# blackfin_c_ethernet.net
KiCad netlist of a schematic drawn in Altium Designer
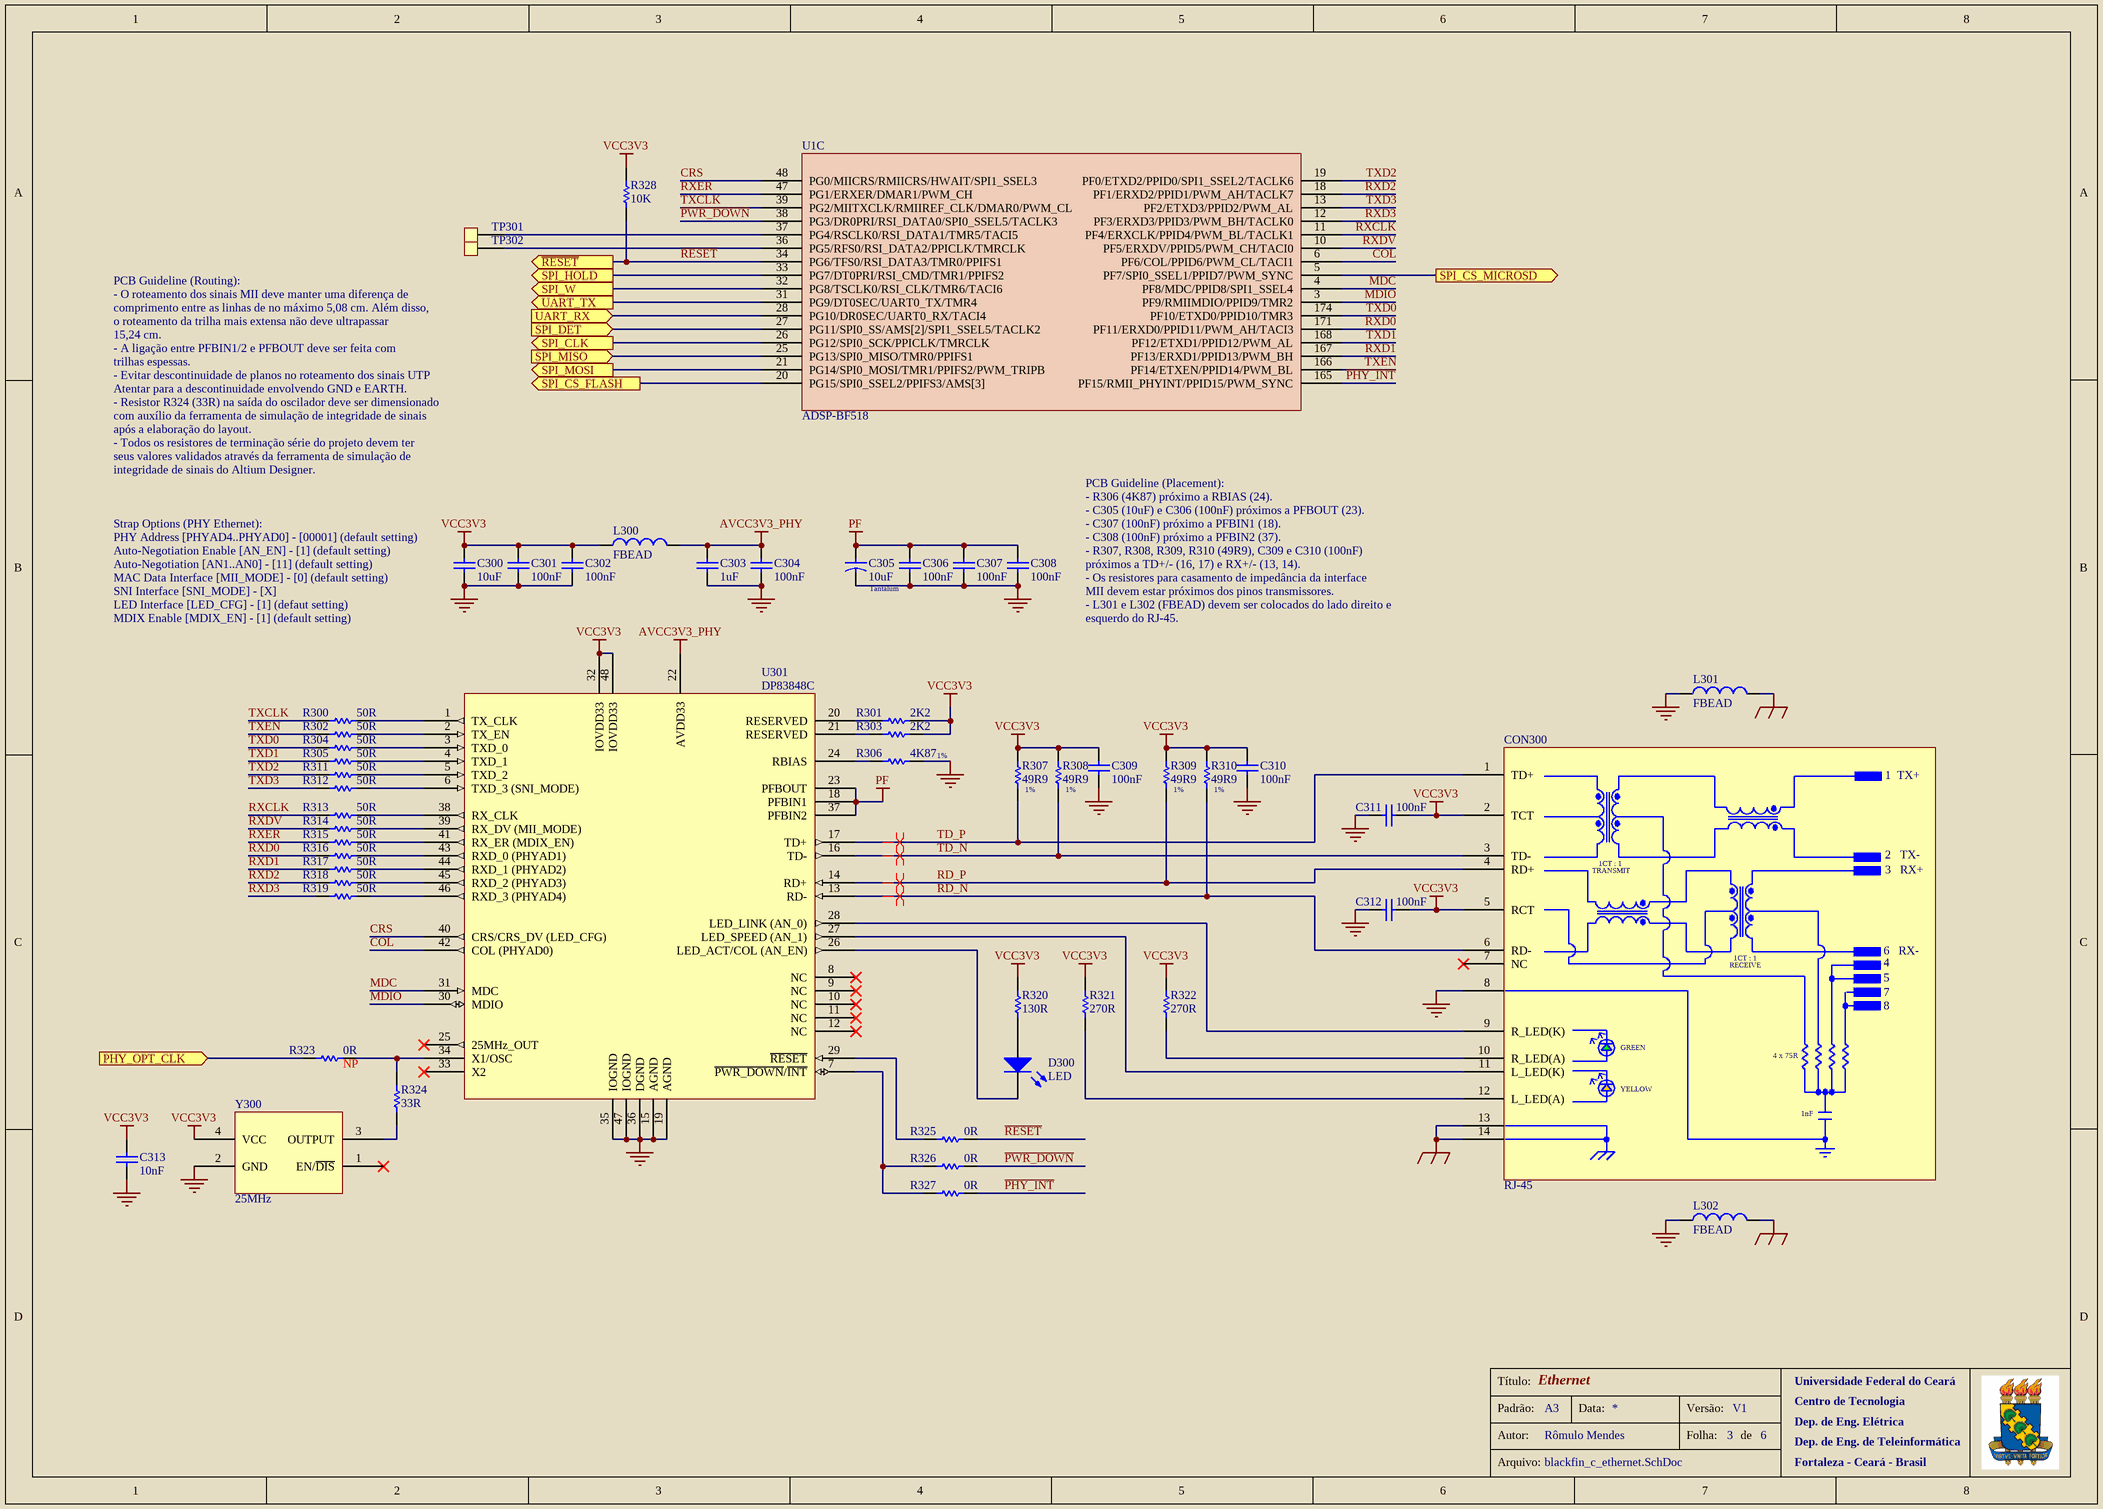
[diagram p0: blackfin_c_ethernet.SchDoc]

(export (version "E")
  (design (tool "Eeschema 10.0.6"))
  (components
    (comp (ref "C300")
      (value "10uF")
      (footprint "blackfin_pcblib:C_0805")
      (fields
        (field (name "EVENDORPART#") "810-C2012Y5V1C106Z")
        (field (name "MANUFACTURER") "TDK")
        (field (name "PART#") "C2012Y5V1C106Z")
      )
      (libsource (lib "blackfin_schlib") (part "Capacitor"))
    )
    (comp (ref "C301")
      (value "100nF")
      (footprint "blackfin_pcblib:C_0603")
      (fields
        (field (name "EVENDORPART#") "81-GRM188R71E104KA01")
        (field (name "MANUFACTURER") "Murata")
        (field (name "PART#") "GRM188R71E104KA01J")
      )
      (libsource (lib "blackfin_schlib") (part "Capacitor"))
    )
    (comp (ref "C302")
      (value "100nF")
      (footprint "blackfin_pcblib:C_0603")
      (fields
        (field (name "EVENDORPART#") "81-GRM188R71E104KA01")
        (field (name "MANUFACTURER") "Murata")
        (field (name "PART#") "GRM188R71E104KA01J")
      )
      (libsource (lib "blackfin_schlib") (part "Capacitor"))
    )
    (comp (ref "C303")
      (value "1uF")
      (footprint "blackfin_pcblib:C_0603")
      (fields
        (field (name "EVENDORPART#") "81-GRM188F51E105ZA12")
        (field (name "MANUFACTURER") "Murata")
        (field (name "PART#") "GRM188F51E105ZA12D")
      )
      (libsource (lib "blackfin_schlib") (part "Capacitor"))
    )
    (comp (ref "C304")
      (value "100nF")
      (footprint "blackfin_pcblib:C_0603")
      (fields
        (field (name "EVENDORPART#") "81-GRM188R71E104KA01")
        (field (name "MANUFACTURER") "Murata")
        (field (name "PART#") "GRM188R71E104KA01J")
      )
      (libsource (lib "blackfin_schlib") (part "Capacitor"))
    )
    (comp (ref "C305")
      (value "10uF")
      (footprint "blackfin_pcblib:C_Case_A")
      (fields
        (field (name "EVENDORPART#") "80-B45196H3106K109")
        (field (name "PART#") "B45196H3106K109V17")
        (field (name "MANUFACTURER") "Kemet")
      )
      (libsource (lib "*") (part "Capacitor_Pol"))
    )
    (comp (ref "C306")
      (value "100nF")
      (footprint "blackfin_pcblib:C_0603")
      (fields
        (field (name "EVENDORPART#") "81-GRM188R71E104KA01")
        (field (name "MANUFACTURER") "Murata")
        (field (name "PART#") "GRM188R71E104KA01J")
      )
      (libsource (lib "blackfin_schlib") (part "Capacitor"))
    )
    (comp (ref "C307")
      (value "100nF")
      (footprint "blackfin_pcblib:C_0603")
      (fields
        (field (name "EVENDORPART#") "81-GRM188R71E104KA01")
        (field (name "MANUFACTURER") "Murata")
        (field (name "PART#") "GRM188R71E104KA01J")
      )
      (libsource (lib "blackfin_schlib") (part "Capacitor"))
    )
    (comp (ref "C308")
      (value "100nF")
      (footprint "blackfin_pcblib:C_0603")
      (fields
        (field (name "EVENDORPART#") "81-GRM188R71E104KA01")
        (field (name "MANUFACTURER") "Murata")
        (field (name "PART#") "GRM188R71E104KA01J")
      )
      (libsource (lib "blackfin_schlib") (part "Capacitor"))
    )
    (comp (ref "C309")
      (value "100nF")
      (footprint "blackfin_pcblib:C_0603")
      (fields
        (field (name "EVENDORPART#") "81-GRM188R71E104KA01")
        (field (name "MANUFACTURER") "Murata")
        (field (name "PART#") "GRM188R71E104KA01J")
      )
      (libsource (lib "blackfin_schlib") (part "Capacitor"))
    )
    (comp (ref "C310")
      (value "100nF")
      (footprint "blackfin_pcblib:C_0603")
      (fields
        (field (name "EVENDORPART#") "81-GRM188R71E104KA01")
        (field (name "MANUFACTURER") "Murata")
        (field (name "PART#") "GRM188R71E104KA01J")
      )
      (libsource (lib "blackfin_schlib") (part "Capacitor"))
    )
    (comp (ref "C311")
      (value "100nF")
      (footprint "blackfin_pcblib:C_0603")
      (fields
        (field (name "EVENDORPART#") "81-GRM188R71E104KA01")
        (field (name "MANUFACTURER") "Murata")
        (field (name "PART#") "GRM188R71E104KA01J")
      )
      (libsource (lib "blackfin_schlib") (part "Capacitor"))
    )
    (comp (ref "C312")
      (value "100nF")
      (footprint "blackfin_pcblib:C_0603")
      (fields
        (field (name "EVENDORPART#") "81-GRM188R71E104KA01")
        (field (name "MANUFACTURER") "Murata")
        (field (name "PART#") "GRM188R71E104KA01J")
      )
      (libsource (lib "blackfin_schlib") (part "Capacitor"))
    )
    (comp (ref "C313")
      (value "10nF")
      (footprint "blackfin_pcblib:C_0603")
      (fields
        (field (name "EVENDORPART#") "77-VJ0603Y103KXAPBC")
        (field (name "MANUFACTURER") "Vishay/Vitramon")
        (field (name "PART#") "VJ0603Y103KXAPW1BC")
      )
      (libsource (lib "blackfin_schlib") (part "Capacitor"))
    )
    (comp (ref "CON300")
      (value "RJ-45")
      (footprint "blackfin_pcblib:RJ-45")
      (fields
        (field (name "EVENDORPART#") "673-J1012F01C")
        (field (name "PART#") "J1012F01C")
        (field (name "MANUFACTURER") "Pulse")
      )
      (libsource (lib "blackfin_schlib") (part "RJ-45"))
    )
    (comp (ref "D300")
      (value "LED")
      (footprint "blackfin_pcblib:LED_0603")
      (description "Green LED")
      (fields (field (name "EVENDORPART#") "638-QTLP600C4") (field (name "MANUFACTURER") "Everlight"))
      (libsource (lib "blackfin_schlib") (part "LED"))
    )
    (comp (ref "L300")
      (value "FBEAD")
      (footprint "blackfin_pcblib:L_0603")
      (fields
        (field (name "EVENDORPART#") "875-MI0603L301R-10")
        (field (name "MANUFACTURER") "Laird Technologies")
        (field (name "PART#") "MI0603L301R-10")
      )
      (libsource (lib "blackfin_schlib") (part "Inductor"))
    )
    (comp (ref "L301")
      (value "FBEAD")
      (footprint "blackfin_pcblib:L_0603")
      (fields
        (field (name "EVENDORPART#") "875-MI0603L301R-10")
        (field (name "MANUFACTURER") "Laird Technologies")
        (field (name "PART#") "MI0603L301R-10")
      )
      (libsource (lib "blackfin_schlib") (part "Inductor"))
    )
    (comp (ref "L302")
      (value "FBEAD")
      (footprint "blackfin_pcblib:L_0603")
      (fields
        (field (name "EVENDORPART#") "875-MI0603L301R-10")
        (field (name "MANUFACTURER") "Laird Technologies")
        (field (name "PART#") "MI0603L301R-10")
      )
      (libsource (lib "blackfin_schlib") (part "Inductor"))
    )
    (comp (ref "R300")
      (value "50R")
      (footprint "blackfin_pcblib:R_0402")
      (fields
        (field (name "EVENDORPART#") "71-CRCW0402-49.9-E3")
        (field (name "PART#") "CRCW040249R9FKED")
        (field (name "MANUFACTURER") "Vishay/Dale")
      )
      (libsource (lib "blackfin_schlib") (part "Resistor"))
    )
    (comp (ref "R301")
      (value "2K2")
      (footprint "blackfin_pcblib:R_0603")
      (fields
        (field (name "EVENDORPART#") "71-CRCW06032K20JNEB")
        (field (name "PART#") "CRCW06032K20JNEB")
        (field (name "MANUFACTURER") "Vishay/Dale")
      )
      (libsource (lib "blackfin_schlib") (part "Resistor"))
    )
    (comp (ref "R302")
      (value "50R")
      (footprint "blackfin_pcblib:R_0402")
      (fields
        (field (name "EVENDORPART#") "71-CRCW0402-49.9-E3")
        (field (name "PART#") "CRCW040249R9FKED")
        (field (name "MANUFACTURER") "Vishay/Dale")
      )
      (libsource (lib "blackfin_schlib") (part "Resistor"))
    )
    (comp (ref "R303")
      (value "2K2")
      (footprint "blackfin_pcblib:R_0603")
      (fields
        (field (name "EVENDORPART#") "71-CRCW06032K20JNEB")
        (field (name "PART#") "CRCW06032K20JNEB")
        (field (name "MANUFACTURER") "Vishay/Dale")
      )
      (libsource (lib "blackfin_schlib") (part "Resistor"))
    )
    (comp (ref "R304")
      (value "50R")
      (footprint "blackfin_pcblib:R_0402")
      (fields
        (field (name "EVENDORPART#") "71-CRCW0402-49.9-E3")
        (field (name "PART#") "CRCW040249R9FKED")
        (field (name "MANUFACTURER") "Vishay/Dale")
      )
      (libsource (lib "blackfin_schlib") (part "Resistor"))
    )
    (comp (ref "R305")
      (value "50R")
      (footprint "blackfin_pcblib:R_0402")
      (fields
        (field (name "EVENDORPART#") "71-CRCW0402-49.9-E3")
        (field (name "PART#") "CRCW040249R9FKED")
        (field (name "MANUFACTURER") "Vishay/Dale")
      )
      (libsource (lib "blackfin_schlib") (part "Resistor"))
    )
    (comp (ref "R306")
      (value "4K87")
      (footprint "blackfin_pcblib:R_0603")
      (fields
        (field (name "EVENDORPART#") "71-CRCW0603-4.87K-E3")
        (field (name "PART#") "CRCW06034K87FKEA")
        (field (name "MANUFACTURER") "Vishay/Dale")
      )
      (libsource (lib "blackfin_schlib") (part "Resistor"))
    )
    (comp (ref "R307")
      (value "49R9")
      (footprint "blackfin_pcblib:R_0603")
      (fields
        (field (name "EVENDORPART#") "71-CRCW060349R9FKEB")
        (field (name "PART#") "CRCW060349R9FKEB")
        (field (name "MANUFACTURER") "Vishay/Dale")
      )
      (libsource (lib "blackfin_schlib") (part "Resistor"))
    )
    (comp (ref "R308")
      (value "49R9")
      (footprint "blackfin_pcblib:R_0603")
      (fields
        (field (name "EVENDORPART#") "71-CRCW060349R9FKEB")
        (field (name "PART#") "CRCW060349R9FKEB")
        (field (name "MANUFACTURER") "Vishay/Dale")
      )
      (libsource (lib "blackfin_schlib") (part "Resistor"))
    )
    (comp (ref "R309")
      (value "49R9")
      (footprint "blackfin_pcblib:R_0603")
      (fields
        (field (name "EVENDORPART#") "71-CRCW060349R9FKEB")
        (field (name "PART#") "CRCW060349R9FKEB")
        (field (name "MANUFACTURER") "Vishay/Dale")
      )
      (libsource (lib "blackfin_schlib") (part "Resistor"))
    )
    (comp (ref "R310")
      (value "49R9")
      (footprint "blackfin_pcblib:R_0603")
      (fields
        (field (name "EVENDORPART#") "71-CRCW060349R9FKEB")
        (field (name "PART#") "CRCW060349R9FKEB")
        (field (name "MANUFACTURER") "Vishay/Dale")
      )
      (libsource (lib "blackfin_schlib") (part "Resistor"))
    )
    (comp (ref "R311")
      (value "50R")
      (footprint "blackfin_pcblib:R_0402")
      (fields
        (field (name "EVENDORPART#") "71-CRCW0402-49.9-E3")
        (field (name "PART#") "CRCW040249R9FKED")
        (field (name "MANUFACTURER") "Vishay/Dale")
      )
      (libsource (lib "blackfin_schlib") (part "Resistor"))
    )
    (comp (ref "R312")
      (value "50R")
      (footprint "blackfin_pcblib:R_0402")
      (fields
        (field (name "EVENDORPART#") "71-CRCW0402-49.9-E3")
        (field (name "PART#") "CRCW040249R9FKED")
        (field (name "MANUFACTURER") "Vishay/Dale")
      )
      (libsource (lib "blackfin_schlib") (part "Resistor"))
    )
    (comp (ref "R313")
      (value "50R")
      (footprint "blackfin_pcblib:R_0402")
      (fields
        (field (name "EVENDORPART#") "71-CRCW0402-49.9-E3")
        (field (name "PART#") "CRCW040249R9FKED")
        (field (name "MANUFACTURER") "Vishay/Dale")
      )
      (libsource (lib "blackfin_schlib") (part "Resistor"))
    )
    (comp (ref "R314")
      (value "50R")
      (footprint "blackfin_pcblib:R_0402")
      (fields
        (field (name "EVENDORPART#") "71-CRCW0402-49.9-E3")
        (field (name "PART#") "CRCW040249R9FKED")
        (field (name "MANUFACTURER") "Vishay/Dale")
      )
      (libsource (lib "blackfin_schlib") (part "Resistor"))
    )
    (comp (ref "R315")
      (value "50R")
      (footprint "blackfin_pcblib:R_0402")
      (fields
        (field (name "EVENDORPART#") "71-CRCW0402-49.9-E3")
        (field (name "PART#") "CRCW040249R9FKED")
        (field (name "MANUFACTURER") "Vishay/Dale")
      )
      (libsource (lib "blackfin_schlib") (part "Resistor"))
    )
    (comp (ref "R316")
      (value "50R")
      (footprint "blackfin_pcblib:R_0402")
      (fields
        (field (name "EVENDORPART#") "71-CRCW0402-49.9-E3")
        (field (name "PART#") "CRCW040249R9FKED")
        (field (name "MANUFACTURER") "Vishay/Dale")
      )
      (libsource (lib "blackfin_schlib") (part "Resistor"))
    )
    (comp (ref "R317")
      (value "50R")
      (footprint "blackfin_pcblib:R_0402")
      (fields
        (field (name "EVENDORPART#") "71-CRCW0402-49.9-E3")
        (field (name "PART#") "CRCW040249R9FKED")
        (field (name "MANUFACTURER") "Vishay/Dale")
      )
      (libsource (lib "blackfin_schlib") (part "Resistor"))
    )
    (comp (ref "R318")
      (value "50R")
      (footprint "blackfin_pcblib:R_0402")
      (fields
        (field (name "EVENDORPART#") "71-CRCW0402-49.9-E3")
        (field (name "PART#") "CRCW040249R9FKED")
        (field (name "MANUFACTURER") "Vishay/Dale")
      )
      (libsource (lib "blackfin_schlib") (part "Resistor"))
    )
    (comp (ref "R319")
      (value "50R")
      (footprint "blackfin_pcblib:R_0402")
      (fields
        (field (name "EVENDORPART#") "71-CRCW0402-49.9-E3")
        (field (name "PART#") "CRCW040249R9FKED")
        (field (name "MANUFACTURER") "Vishay/Dale")
      )
      (libsource (lib "blackfin_schlib") (part "Resistor"))
    )
    (comp (ref "R320")
      (value "130R")
      (footprint "blackfin_pcblib:R_0603")
      (fields
        (field (name "EVENDORPART#") "71-CRCW0603-130-E3")
        (field (name "PART#") "CRCW0603130RFKEA")
        (field (name "MANUFACTURER") "Vishay/Dale")
      )
      (libsource (lib "blackfin_schlib") (part "Resistor"))
    )
    (comp (ref "R321")
      (value "270R")
      (footprint "blackfin_pcblib:R_0603")
      (fields
        (field (name "EVENDORPART#") "71-CRCW0603-270-E3")
        (field (name "PART#") "CRCW0603270RFKEA")
        (field (name "MANUFACTURER") "Vishay/Dale")
      )
      (libsource (lib "blackfin_schlib") (part "Resistor"))
    )
    (comp (ref "R322")
      (value "270R")
      (footprint "blackfin_pcblib:R_0603")
      (fields
        (field (name "EVENDORPART#") "71-CRCW0603-270-E3")
        (field (name "PART#") "CRCW0603270RFKEA")
        (field (name "MANUFACTURER") "Vishay/Dale")
      )
      (libsource (lib "blackfin_schlib") (part "Resistor"))
    )
    (comp (ref "R323")
      (value "0R")
      (footprint "blackfin_pcblib:R_0603")
      (fields
        (field (name "EVENDORPART#") "71-CRCW06030000Z0EB")
        (field (name "PART#") "CRCW06030000Z0EB")
        (field (name "MANUFACTURER") "Vishay/Dale")
      )
      (libsource (lib "blackfin_schlib") (part "Resistor"))
    )
    (comp (ref "R324")
      (value "33R")
      (footprint "blackfin_pcblib:R_0402")
      (fields
        (field (name "EVENDORPART#") "71-CRCW0402J-33-E3")
        (field (name "PART#") "CRCW040233R0JNED")
        (field (name "MANUFACTURER") "Vishay/Dale")
      )
      (libsource (lib "blackfin_schlib") (part "Resistor"))
    )
    (comp (ref "R325")
      (value "0R")
      (footprint "blackfin_pcblib:R_0603")
      (fields
        (field (name "EVENDORPART#") "71-CRCW06030000Z0EB")
        (field (name "PART#") "CRCW06030000Z0EB")
        (field (name "MANUFACTURER") "Vishay/Dale")
      )
      (libsource (lib "blackfin_schlib") (part "Resistor"))
    )
    (comp (ref "R326")
      (value "0R")
      (footprint "blackfin_pcblib:R_0603")
      (fields
        (field (name "EVENDORPART#") "71-CRCW06030000Z0EB")
        (field (name "PART#") "CRCW06030000Z0EB")
        (field (name "MANUFACTURER") "Vishay/Dale")
      )
      (libsource (lib "blackfin_schlib") (part "Resistor"))
    )
    (comp (ref "R327")
      (value "0R")
      (footprint "blackfin_pcblib:R_0603")
      (fields
        (field (name "EVENDORPART#") "71-CRCW06030000Z0EB")
        (field (name "PART#") "CRCW06030000Z0EB")
        (field (name "MANUFACTURER") "Vishay/Dale")
      )
      (libsource (lib "blackfin_schlib") (part "Resistor"))
    )
    (comp (ref "R328")
      (value "10K")
      (footprint "blackfin_pcblib:R_0603")
      (fields
        (field (name "EVENDORPART#") "71-CRCW0603-10K-E3")
        (field (name "PART#") "CRCW060310K0FKEA")
        (field (name "MANUFACTURER") "Vishay/Dale")
      )
      (libsource (lib "blackfin_schlib") (part "Resistor"))
    )
    (comp (ref "TP301")
      (value "Test Point")
      (footprint "blackfin_pcblib:Test Point")
      (fields (field (name "EVENDORPART#") "NÃO SE APLICA"))
      (libsource (lib "blackfin_schlib") (part "Test Point"))
    )
    (comp (ref "TP302")
      (value "Test Point")
      (footprint "blackfin_pcblib:Test Point")
      (fields (field (name "EVENDORPART#") "NÃO SE APLICA"))
      (libsource (lib "blackfin_schlib") (part "Test Point"))
    )
    (comp (ref "U1")
      (value "ADSP-BF518")
      (footprint "blackfin_pcblib:LQFP-176")
      (fields (field (name "EVENDORPART#") "ADSP-BF518BSWZ-4") (field (name "MANUFACTURER") "Analog Devices"))
      (libsource (lib "blackfin_schlib") (part "ADSP-BF518"))
    )
    (comp (ref "U301")
      (value "DP83848C")
      (footprint "blackfin_pcblib:LQFP-48")
      (fields
        (field (name "MANUFACTURER") "National Semiconductor")
        (field (name "PART#") "DP83848CVV/NOPB")
        (field (name "EVENDORPART#") "DP83848CVV-ND")
      )
      (libsource (lib "blackfin_schlib") (part "DP83848C"))
    )
    (comp (ref "Y300")
      (value "25MHz")
      (footprint "blackfin_pcblib:OSC_25MHz")
      (fields
        (field (name "EVENDORPART#") "815-ASV-25-EJ-T")
        (field (name "PART#") "ASV-25.000MHZ-EJ-T")
        (field (name "MANUFACTURER") "ABRACON")
      )
      (libsource (lib "blackfin_schlib") (part "Oscillator_25MHz"))
    )
  )
  (nets
    (net (code "1") (name "/COL") (class "Default")
      (node (ref "U1") (pin "6") (pinfunction "PF6/COL/PPID6/PWM_CL/TACI1_6") (pintype "passive"))
      (node (ref "U301") (pin "42") (pinfunction "COL_(PHYAD0)_42") (pintype "output"))
    )
    (net (code "2") (name "/CRS") (class "Default")
      (node (ref "U1") (pin "48") (pinfunction "PG0/MIICRS/RMIICRS/HWAIT/SPI1_SSEL3_48") (pintype "passive"))
      (node (ref "U301") (pin "40") (pinfunction "CRS/CRS_DV_(LED_CFG)_40") (pintype "output"))
    )
    (net (code "3") (name "/MDC") (class "Default")
      (node (ref "U1") (pin "4") (pinfunction "PF8/MDC/PPID8/SPI1_SSEL4_4") (pintype "passive"))
      (node (ref "U301") (pin "31") (pinfunction "MDC_31") (pintype "input"))
    )
    (net (code "4") (name "/MDIO") (class "Default")
      (node (ref "U1") (pin "3") (pinfunction "PF9/RMIIMDIO/PPID9/TMR2_3") (pintype "passive"))
      (node (ref "U301") (pin "30") (pinfunction "MDIO_30") (pintype "bidirectional"))
    )
    (net (code "5") (name "/PHY_OPT_CLK") (class "Default")
      (node (ref "R323") (pin "1") (pinfunction "1_1") (pintype "passive"))
    )
    (net (code "6") (name "/RD_N") (class "Default")
      (node (ref "CON300") (pin "6") (pinfunction "RD-_6") (pintype "passive"))
      (node (ref "R310") (pin "1") (pinfunction "1_1") (pintype "passive"))
      (node (ref "U301") (pin "13") (pinfunction "RD-_13") (pintype "input"))
    )
    (net (code "7") (name "/RD_P") (class "Default")
      (node (ref "CON300") (pin "4") (pinfunction "RD+_4") (pintype "passive"))
      (node (ref "R309") (pin "1") (pinfunction "1_1") (pintype "passive"))
      (node (ref "U301") (pin "14") (pinfunction "RD+_14") (pintype "input"))
    )
    (net (code "8") (name "/RXCLK") (class "Default")
      (node (ref "R313") (pin "1") (pinfunction "1_1") (pintype "passive"))
      (node (ref "U1") (pin "11") (pinfunction "PF4/ERXCLK/PPID4/PWM_BL/TACLK1_11") (pintype "passive"))
    )
    (net (code "9") (name "/RXD0") (class "Default")
      (node (ref "R316") (pin "1") (pinfunction "1_1") (pintype "passive"))
      (node (ref "U1") (pin "171") (pinfunction "PF11/ERXD0/PPID11/PWM_AH/TACI3_171") (pintype "passive"))
    )
    (net (code "10") (name "/RXD1") (class "Default")
      (node (ref "R317") (pin "1") (pinfunction "1_1") (pintype "passive"))
      (node (ref "U1") (pin "167") (pinfunction "PF13/ERXD1/PPID13/PWM_BH_167") (pintype "passive"))
    )
    (net (code "11") (name "/RXD2") (class "Default")
      (node (ref "R318") (pin "1") (pinfunction "1_1") (pintype "passive"))
      (node (ref "U1") (pin "18") (pinfunction "PF1/ERXD2/PPID1/PWM_AH/TACLK7_18") (pintype "passive"))
    )
    (net (code "12") (name "/RXD3") (class "Default")
      (node (ref "R319") (pin "1") (pinfunction "1_1") (pintype "passive"))
      (node (ref "U1") (pin "12") (pinfunction "PF3/ERXD3/PPID3/PWM_BH/TACLK0_12") (pintype "passive"))
    )
    (net (code "13") (name "/RXDV") (class "Default")
      (node (ref "R314") (pin "1") (pinfunction "1_1") (pintype "passive"))
      (node (ref "U1") (pin "10") (pinfunction "PF5/ERXDV/PPID5/PWM_CH/TACI0_10") (pintype "passive"))
    )
    (net (code "14") (name "/RXER") (class "Default")
      (node (ref "R315") (pin "1") (pinfunction "1_1") (pintype "passive"))
      (node (ref "U1") (pin "47") (pinfunction "PG1/ERXER/DMAR1/PWM_CH_47") (pintype "passive"))
    )
    (net (code "15") (name "/SPI_CLK") (class "Default")
      (node (ref "U1") (pin "26") (pinfunction "PG12/SPI0_SCK/PPICLK/TMRCLK_26") (pintype "passive"))
    )
    (net (code "16") (name "/SPI_CS_FLASH") (class "Default")
      (node (ref "U1") (pin "20") (pinfunction "PG15/SPI0_SSEL2/PPIFS3/AMS[3]_20") (pintype "passive"))
    )
    (net (code "17") (name "/SPI_CS_MICROSD") (class "Default")
      (node (ref "U1") (pin "5") (pinfunction "PF7/SPI0_SSEL1/PPID7/PWM_SYNC_5") (pintype "passive"))
    )
    (net (code "18") (name "/SPI_DET") (class "Default")
      (node (ref "U1") (pin "27") (pinfunction "PG11/SPI0_SS/AMS[2]/SPI1_SSEL5/TACLK2_27") (pintype "passive"))
    )
    (net (code "19") (name "/SPI_HOLD") (class "Default")
      (node (ref "U1") (pin "33") (pinfunction "PG7/DT0PRI/RSI_CMD/TMR1/PPIFS2_33") (pintype "passive"))
    )
    (net (code "20") (name "/SPI_MISO") (class "Default")
      (node (ref "U1") (pin "25") (pinfunction "PG13/SPI0_MISO/TMR0/PPIFS1_25") (pintype "passive"))
    )
    (net (code "21") (name "/SPI_MOSI") (class "Default")
      (node (ref "U1") (pin "21") (pinfunction "PG14/SPI0_MOSI/TMR1/PPIFS2/PWM_TRIPB_21") (pintype "passive"))
    )
    (net (code "22") (name "/SPI_W") (class "Default")
      (node (ref "U1") (pin "32") (pinfunction "PG8/TSCLK0/RSI_CLK/TMR6/TACI6_32") (pintype "passive"))
    )
    (net (code "23") (name "/TD_N") (class "Default")
      (node (ref "CON300") (pin "3") (pinfunction "TD-_3") (pintype "passive"))
      (node (ref "R308") (pin "1") (pinfunction "1_1") (pintype "passive"))
      (node (ref "U301") (pin "16") (pinfunction "TD-_16") (pintype "output"))
    )
    (net (code "24") (name "/TD_P") (class "Default")
      (node (ref "CON300") (pin "1") (pinfunction "TD+_1") (pintype "passive"))
      (node (ref "R307") (pin "1") (pinfunction "1_1") (pintype "passive"))
      (node (ref "U301") (pin "17") (pinfunction "TD+_17") (pintype "output"))
    )
    (net (code "25") (name "/TXCLK") (class "Default")
      (node (ref "R300") (pin "1") (pinfunction "1_1") (pintype "passive"))
      (node (ref "U1") (pin "39") (pinfunction "PG2/MIITXCLK/RMIIREF_CLK/DMAR0/PWM_CL_39") (pintype "passive"))
    )
    (net (code "26") (name "/TXD0") (class "Default")
      (node (ref "R304") (pin "1") (pinfunction "1_1") (pintype "passive"))
      (node (ref "U1") (pin "174") (pinfunction "PF10/ETXD0/PPID10/TMR3_174") (pintype "passive"))
    )
    (net (code "27") (name "/TXD1") (class "Default")
      (node (ref "R305") (pin "1") (pinfunction "1_1") (pintype "passive"))
      (node (ref "U1") (pin "168") (pinfunction "PF12/ETXD1/PPID12/PWM_AL_168") (pintype "passive"))
    )
    (net (code "28") (name "/TXD2") (class "Default")
      (node (ref "R311") (pin "1") (pinfunction "1_1") (pintype "passive"))
      (node (ref "U1") (pin "19") (pinfunction "PF0/ETXD2/PPID0/SPI1_SSEL2/TACLK6_19") (pintype "passive"))
    )
    (net (code "29") (name "/TXD3") (class "Default")
      (node (ref "R312") (pin "1") (pinfunction "1_1") (pintype "passive"))
      (node (ref "U1") (pin "13") (pinfunction "PF2/ETXD3/PPID2/PWM_AL_13") (pintype "passive"))
    )
    (net (code "30") (name "/TXEN") (class "Default")
      (node (ref "R302") (pin "1") (pinfunction "1_1") (pintype "passive"))
      (node (ref "U1") (pin "166") (pinfunction "PF14/ETXEN/PPID14/PWM_BL_166") (pintype "passive"))
    )
    (net (code "31") (name "/UART_RX") (class "Default")
      (node (ref "U1") (pin "28") (pinfunction "PG10/DR0SEC/UART0_RX/TACI4_28") (pintype "passive"))
    )
    (net (code "32") (name "/UART_TX") (class "Default")
      (node (ref "U1") (pin "31") (pinfunction "PG9/DT0SEC/UART0_TX/TMR4_31") (pintype "passive"))
    )
    (net (code "33") (name "/~{PHY_INT}") (class "Default")
      (node (ref "R327") (pin "2") (pinfunction "2_2") (pintype "passive"))
      (node (ref "U1") (pin "165") (pinfunction "PF15/RMII_PHYINT/PPID15/PWM_SYNC_165") (pintype "passive"))
    )
    (net (code "34") (name "/~{PWR_DOWN}") (class "Default")
      (node (ref "R326") (pin "2") (pinfunction "2_2") (pintype "passive"))
      (node (ref "U1") (pin "38") (pinfunction "PG3/DR0PRI/RSI_DATA0/SPI0_SSEL5/TACLK3_38") (pintype "passive"))
    )
    (net (code "35") (name "/~{RESET}") (class "Default")
      (node (ref "R325") (pin "2") (pinfunction "2_2") (pintype "passive"))
      (node (ref "R328") (pin "2") (pinfunction "2_2") (pintype "passive"))
      (node (ref "U1") (pin "34") (pinfunction "PG6/TFS0/RSI_DATA3/TMR0/PPIFS1_34") (pintype "passive"))
    )
    (net (code "36") (name "AVCC3V3_PHY") (class "Default")
      (node (ref "C303") (pin "2") (pinfunction "2_2") (pintype "passive"))
      (node (ref "C304") (pin "2") (pinfunction "2_2") (pintype "passive"))
      (node (ref "L300") (pin "2") (pinfunction "2_2") (pintype "passive"))
      (node (ref "U301") (pin "22") (pinfunction "AVDD33_22") (pintype "power_in"))
    )
    (net (code "37") (name "EARTH_ETH") (class "Default")
      (node (ref "CON300") (pin "13") (pinfunction "GND_13") (pintype "passive"))
      (node (ref "CON300") (pin "14") (pinfunction "GND_14") (pintype "passive"))
      (node (ref "L301") (pin "2") (pinfunction "2_2") (pintype "passive"))
      (node (ref "L302") (pin "2") (pinfunction "2_2") (pintype "passive"))
    )
    (net (code "38") (name "GND") (class "Default")
      (node (ref "C300") (pin "1") (pinfunction "1_1") (pintype "passive"))
      (node (ref "C301") (pin "1") (pinfunction "1_1") (pintype "passive"))
      (node (ref "C302") (pin "1") (pinfunction "1_1") (pintype "passive"))
      (node (ref "C303") (pin "1") (pinfunction "1_1") (pintype "passive"))
      (node (ref "C304") (pin "1") (pinfunction "1_1") (pintype "passive"))
      (node (ref "C305") (pin "2") (pinfunction "2_2") (pintype "passive"))
      (node (ref "C306") (pin "1") (pinfunction "1_1") (pintype "passive"))
      (node (ref "C307") (pin "1") (pinfunction "1_1") (pintype "passive"))
      (node (ref "C308") (pin "1") (pinfunction "1_1") (pintype "passive"))
      (node (ref "C309") (pin "1") (pinfunction "1_1") (pintype "passive"))
      (node (ref "C310") (pin "1") (pinfunction "1_1") (pintype "passive"))
      (node (ref "C311") (pin "2") (pinfunction "2_2") (pintype "passive"))
      (node (ref "C312") (pin "2") (pinfunction "2_2") (pintype "passive"))
      (node (ref "C313") (pin "1") (pinfunction "1_1") (pintype "passive"))
      (node (ref "CON300") (pin "8") (pinfunction "GND_8") (pintype "passive"))
      (node (ref "L301") (pin "1") (pinfunction "1_1") (pintype "passive"))
      (node (ref "L302") (pin "1") (pinfunction "1_1") (pintype "passive"))
      (node (ref "R306") (pin "1") (pinfunction "1_1") (pintype "passive"))
      (node (ref "U301") (pin "15") (pinfunction "AGND_15") (pintype "power_in"))
      (node (ref "U301") (pin "19") (pinfunction "AGND_19") (pintype "power_in"))
      (node (ref "U301") (pin "35") (pinfunction "IOGND_35") (pintype "power_in"))
      (node (ref "U301") (pin "36") (pinfunction "DGND_36") (pintype "power_in"))
      (node (ref "U301") (pin "47") (pinfunction "IOGND_47") (pintype "power_in"))
      (node (ref "Y300") (pin "2") (pinfunction "GND_2") (pintype "passive"))
    )
    (net (code "39") (name "Net-(CON300-L_LED(A))") (class "Default")
      (node (ref "CON300") (pin "12") (pinfunction "L_LED(A)_12") (pintype "passive"))
      (node (ref "R321") (pin "1") (pinfunction "1_1") (pintype "passive"))
    )
    (net (code "40") (name "Net-(CON300-L_LED(K))") (class "Default")
      (node (ref "CON300") (pin "11") (pinfunction "L_LED(K)_11") (pintype "passive"))
      (node (ref "U301") (pin "27") (pinfunction "LED_SPEED_(AN_1)_27") (pintype "output"))
    )
    (net (code "41") (name "Net-(CON300-R_LED(A))") (class "Default")
      (node (ref "CON300") (pin "10") (pinfunction "R_LED(A)_10") (pintype "passive"))
      (node (ref "R322") (pin "1") (pinfunction "1_1") (pintype "passive"))
    )
    (net (code "42") (name "Net-(CON300-R_LED(K))") (class "Default")
      (node (ref "CON300") (pin "9") (pinfunction "R_LED(K)_9") (pintype "passive"))
      (node (ref "U301") (pin "28") (pinfunction "LED_LINK_(AN_0)_28") (pintype "output"))
    )
    (net (code "43") (name "Net-(D300-A)") (class "Default")
      (node (ref "D300") (pin "1") (pinfunction "A_1") (pintype "passive"))
      (node (ref "R320") (pin "1") (pinfunction "1_1") (pintype "passive"))
    )
    (net (code "44") (name "Net-(D300-K)") (class "Default")
      (node (ref "D300") (pin "2") (pinfunction "K_2") (pintype "passive"))
      (node (ref "U301") (pin "26") (pinfunction "LED_ACT/COL_(AN_EN)_26") (pintype "output"))
    )
    (net (code "45") (name "Net-(R301-Pad2)") (class "Default")
      (node (ref "R301") (pin "2") (pinfunction "2_2") (pintype "passive"))
      (node (ref "U301") (pin "20") (pinfunction "RESERVED_20") (pintype "passive"))
    )
    (net (code "46") (name "Net-(R303-Pad2)") (class "Default")
      (node (ref "R303") (pin "2") (pinfunction "2_2") (pintype "passive"))
      (node (ref "U301") (pin "21") (pinfunction "RESERVED_21") (pintype "passive"))
    )
    (net (code "47") (name "Net-(U1C-PG4{slash}RSCLK0{slash}RSI_DATA1{slash}TMR5{slash}TACI5)") (class "Default")
      (node (ref "TP301") (pin "1") (pinfunction "1_1") (pintype "passive"))
      (node (ref "U1") (pin "37") (pinfunction "PG4/RSCLK0/RSI_DATA1/TMR5/TACI5_37") (pintype "passive"))
    )
    (net (code "48") (name "Net-(U1C-PG5{slash}RFS0{slash}RSI_DATA2{slash}PPICLK{slash}TMRCLK)") (class "Default")
      (node (ref "TP302") (pin "1") (pinfunction "1_1") (pintype "passive"))
      (node (ref "U1") (pin "36") (pinfunction "PG5/RFS0/RSI_DATA2/PPICLK/TMRCLK_36") (pintype "passive"))
    )
    (net (code "49") (name "Net-(U301-RBIAS)") (class "Default")
      (node (ref "R306") (pin "2") (pinfunction "2_2") (pintype "passive"))
      (node (ref "U301") (pin "24") (pinfunction "RBIAS_24") (pintype "passive"))
    )
    (net (code "50") (name "Net-(U301-RXD_0_(PHYAD1))") (class "Default")
      (node (ref "R316") (pin "2") (pinfunction "2_2") (pintype "passive"))
      (node (ref "U301") (pin "43") (pinfunction "RXD_0_(PHYAD1)_43") (pintype "output"))
    )
    (net (code "51") (name "Net-(U301-RXD_1_(PHYAD2))") (class "Default")
      (node (ref "R317") (pin "2") (pinfunction "2_2") (pintype "passive"))
      (node (ref "U301") (pin "44") (pinfunction "RXD_1_(PHYAD2)_44") (pintype "output"))
    )
    (net (code "52") (name "Net-(U301-RXD_2_(PHYAD3))") (class "Default")
      (node (ref "R318") (pin "2") (pinfunction "2_2") (pintype "passive"))
      (node (ref "U301") (pin "45") (pinfunction "RXD_2_(PHYAD3)_45") (pintype "output"))
    )
    (net (code "53") (name "Net-(U301-RXD_3_(PHYAD4))") (class "Default")
      (node (ref "R319") (pin "2") (pinfunction "2_2") (pintype "passive"))
      (node (ref "U301") (pin "46") (pinfunction "RXD_3_(PHYAD4)_46") (pintype "output"))
    )
    (net (code "54") (name "Net-(U301-RX_CLK)") (class "Default")
      (node (ref "R313") (pin "2") (pinfunction "2_2") (pintype "passive"))
      (node (ref "U301") (pin "38") (pinfunction "RX_CLK_38") (pintype "output"))
    )
    (net (code "55") (name "Net-(U301-RX_DV_(MII_MODE))") (class "Default")
      (node (ref "R314") (pin "2") (pinfunction "2_2") (pintype "passive"))
      (node (ref "U301") (pin "39") (pinfunction "RX_DV_(MII_MODE)_39") (pintype "output"))
    )
    (net (code "56") (name "Net-(U301-RX_ER_(MDIX_EN))") (class "Default")
      (node (ref "R315") (pin "2") (pinfunction "2_2") (pintype "passive"))
      (node (ref "U301") (pin "41") (pinfunction "RX_ER_(MDIX_EN)_41") (pintype "output"))
    )
    (net (code "57") (name "Net-(U301-TXD_0)") (class "Default")
      (node (ref "R304") (pin "2") (pinfunction "2_2") (pintype "passive"))
      (node (ref "U301") (pin "3") (pinfunction "TXD_0_3") (pintype "input"))
    )
    (net (code "58") (name "Net-(U301-TXD_1)") (class "Default")
      (node (ref "R305") (pin "2") (pinfunction "2_2") (pintype "passive"))
      (node (ref "U301") (pin "4") (pinfunction "TXD_1_4") (pintype "input"))
    )
    (net (code "59") (name "Net-(U301-TXD_2)") (class "Default")
      (node (ref "R311") (pin "2") (pinfunction "2_2") (pintype "passive"))
      (node (ref "U301") (pin "5") (pinfunction "TXD_2_5") (pintype "input"))
    )
    (net (code "60") (name "Net-(U301-TXD_3_(SNI_MODE))") (class "Default")
      (node (ref "R312") (pin "2") (pinfunction "2_2") (pintype "passive"))
      (node (ref "U301") (pin "6") (pinfunction "TXD_3_(SNI_MODE)_6") (pintype "input"))
    )
    (net (code "61") (name "Net-(U301-TX_CLK)") (class "Default")
      (node (ref "R300") (pin "2") (pinfunction "2_2") (pintype "passive"))
      (node (ref "U301") (pin "1") (pinfunction "TX_CLK_1") (pintype "output"))
    )
    (net (code "62") (name "Net-(U301-TX_EN)") (class "Default")
      (node (ref "R302") (pin "2") (pinfunction "2_2") (pintype "passive"))
      (node (ref "U301") (pin "2") (pinfunction "TX_EN_2") (pintype "input"))
    )
    (net (code "63") (name "Net-(U301-X1{slash}OSC)") (class "Default")
      (node (ref "R323") (pin "2") (pinfunction "2_2") (pintype "passive"))
      (node (ref "R324") (pin "2") (pinfunction "2_2") (pintype "passive"))
      (node (ref "U301") (pin "34") (pinfunction "X1/OSC_34") (pintype "passive"))
    )
    (net (code "64") (name "Net-(U301-~{PWR_DOWN}{slash}~{INT})") (class "Default")
      (node (ref "R326") (pin "1") (pinfunction "1_1") (pintype "passive"))
      (node (ref "R327") (pin "1") (pinfunction "1_1") (pintype "passive"))
      (node (ref "U301") (pin "7") (pinfunction "~{PWR_DOWN}/~{INT}_7") (pintype "bidirectional"))
    )
    (net (code "65") (name "Net-(U301-~{RESET})") (class "Default")
      (node (ref "R325") (pin "1") (pinfunction "1_1") (pintype "passive"))
      (node (ref "U301") (pin "29") (pinfunction "~{RESET}_29") (pintype "input"))
    )
    (net (code "66") (name "Net-(Y300-OUTPUT)") (class "Default")
      (node (ref "R324") (pin "1") (pinfunction "1_1") (pintype "passive"))
      (node (ref "Y300") (pin "3") (pinfunction "OUTPUT_3") (pintype "passive"))
    )
    (net (code "67") (name "PF") (class "Default")
      (node (ref "C305") (pin "1") (pinfunction "1_1") (pintype "passive"))
      (node (ref "C306") (pin "2") (pinfunction "2_2") (pintype "passive"))
      (node (ref "C307") (pin "2") (pinfunction "2_2") (pintype "passive"))
      (node (ref "C308") (pin "2") (pinfunction "2_2") (pintype "passive"))
      (node (ref "U301") (pin "18") (pinfunction "PFBIN1_18") (pintype "passive"))
      (node (ref "U301") (pin "23") (pinfunction "PFBOUT_23") (pintype "passive"))
      (node (ref "U301") (pin "37") (pinfunction "PFBIN2_37") (pintype "passive"))
    )
    (net (code "68") (name "VCC3V3") (class "Default")
      (node (ref "C300") (pin "2") (pinfunction "2_2") (pintype "passive"))
      (node (ref "C301") (pin "2") (pinfunction "2_2") (pintype "passive"))
      (node (ref "C302") (pin "2") (pinfunction "2_2") (pintype "passive"))
      (node (ref "C309") (pin "2") (pinfunction "2_2") (pintype "passive"))
      (node (ref "C310") (pin "2") (pinfunction "2_2") (pintype "passive"))
      (node (ref "C311") (pin "1") (pinfunction "1_1") (pintype "passive"))
      (node (ref "C312") (pin "1") (pinfunction "1_1") (pintype "passive"))
      (node (ref "C313") (pin "2") (pinfunction "2_2") (pintype "passive"))
      (node (ref "CON300") (pin "2") (pinfunction "TCT_2") (pintype "passive"))
      (node (ref "CON300") (pin "5") (pinfunction "RCT_5") (pintype "passive"))
      (node (ref "L300") (pin "1") (pinfunction "1_1") (pintype "passive"))
      (node (ref "R301") (pin "1") (pinfunction "1_1") (pintype "passive"))
      (node (ref "R303") (pin "1") (pinfunction "1_1") (pintype "passive"))
      (node (ref "R307") (pin "2") (pinfunction "2_2") (pintype "passive"))
      (node (ref "R308") (pin "2") (pinfunction "2_2") (pintype "passive"))
      (node (ref "R309") (pin "2") (pinfunction "2_2") (pintype "passive"))
      (node (ref "R310") (pin "2") (pinfunction "2_2") (pintype "passive"))
      (node (ref "R320") (pin "2") (pinfunction "2_2") (pintype "passive"))
      (node (ref "R321") (pin "2") (pinfunction "2_2") (pintype "passive"))
      (node (ref "R322") (pin "2") (pinfunction "2_2") (pintype "passive"))
      (node (ref "R328") (pin "1") (pinfunction "1_1") (pintype "passive"))
      (node (ref "U301") (pin "32") (pinfunction "IOVDD33_32") (pintype "power_in"))
      (node (ref "U301") (pin "48") (pinfunction "IOVDD33_48") (pintype "power_in"))
      (node (ref "Y300") (pin "4") (pinfunction "VCC_4") (pintype "passive"))
    )
    (net (code "69") (name "unconnected-(CON300-NC-Pad7)") (class "Default")
      (node (ref "CON300") (pin "7") (pinfunction "NC_7") (pintype "passive+no_connect"))
    )
    (net (code "70") (name "unconnected-(U301-25MHz_OUT-Pad25)") (class "Default")
      (node (ref "U301") (pin "25") (pinfunction "25MHz_OUT_25") (pintype "output+no_connect"))
    )
    (net (code "71") (name "unconnected-(U301-NC-Pad8)") (class "Default")
      (node (ref "U301") (pin "8") (pinfunction "NC_8") (pintype "passive+no_connect"))
    )
    (net (code "72") (name "unconnected-(U301-NC-Pad9)") (class "Default")
      (node (ref "U301") (pin "9") (pinfunction "NC_9") (pintype "passive+no_connect"))
    )
    (net (code "73") (name "unconnected-(U301-NC-Pad10)") (class "Default")
      (node (ref "U301") (pin "10") (pinfunction "NC_10") (pintype "passive+no_connect"))
    )
    (net (code "74") (name "unconnected-(U301-NC-Pad11)") (class "Default")
      (node (ref "U301") (pin "11") (pinfunction "NC_11") (pintype "passive+no_connect"))
    )
    (net (code "75") (name "unconnected-(U301-NC-Pad12)") (class "Default")
      (node (ref "U301") (pin "12") (pinfunction "NC_12") (pintype "passive+no_connect"))
    )
    (net (code "76") (name "unconnected-(U301-X2-Pad33)") (class "Default")
      (node (ref "U301") (pin "33") (pinfunction "X2_33") (pintype "passive+no_connect"))
    )
    (net (code "77") (name "unconnected-(Y300-EN{slash}~{DIS}-Pad1)") (class "Default")
      (node (ref "Y300") (pin "1") (pinfunction "EN/~{DIS}_1") (pintype "passive+no_connect"))
    )
  )
)
